# device-radiator-fan.net
KiCad netlist of a schematic drawn in Altium Designer
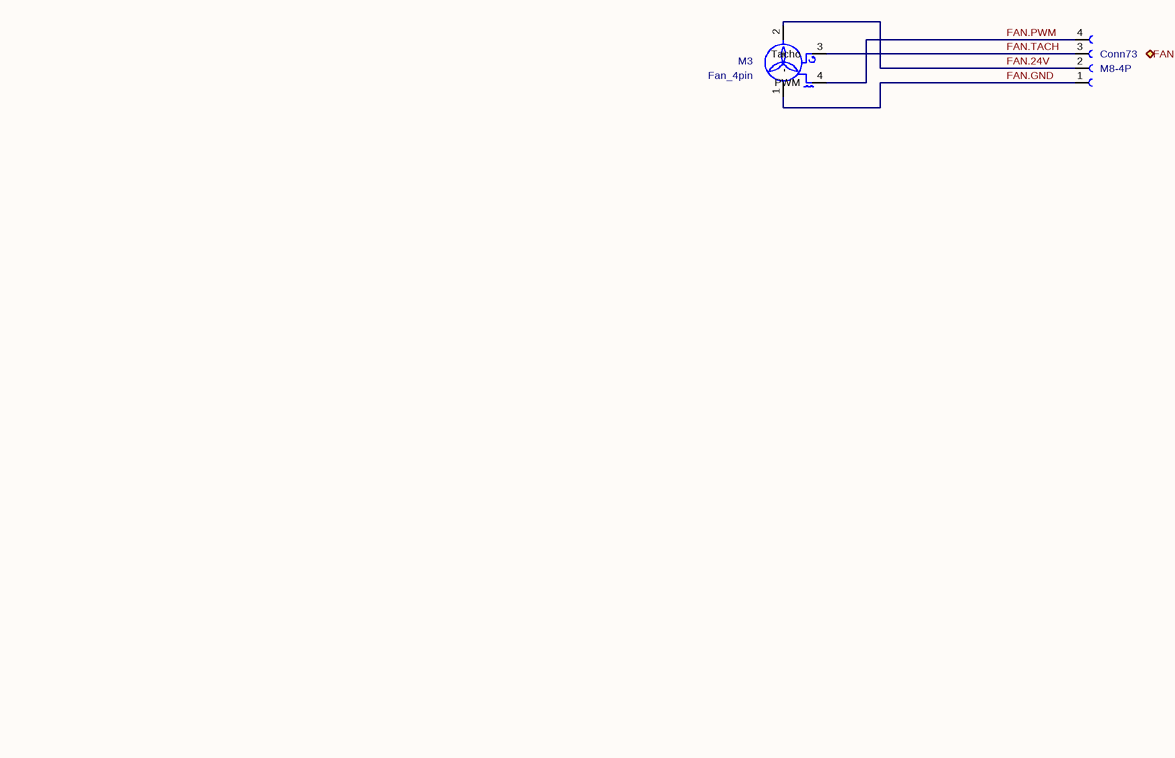
[diagram p0: device-radiator-fan.SchDoc]

(export (version "E")
  (design (tool "Eeschema 10.0.6"))
  (components
    (comp (ref "Conn73")
      (value "Deutsch_DTM_4S_Pin")
      (fields (field (name "P/N") "M8-4P"))
      (libsource (lib "Connectors_SUFST") (part "Deutsch_DTM_4S_Pin"))
    )
    (comp (ref "M3")
      (value "Fan_4pin")
      (footprint "FanPinHeader_1x04_P2.54mm_Vertical")
      (description "Fan, tacho output, PWM input, 4-pin connector")
      (libsource (lib "Motor") (part "Fan_4pin"))
    )
  )
  (nets
    (net (code "2") (name "/FAN.24V") (class "Default")
      (node (ref "Conn73") (pin "2") (pinfunction "2_2") (pintype "passive"))
      (node (ref "M3") (pin "2") (pinfunction "+_2") (pintype "passive"))
    )
    (net (code "3") (name "/FAN.GND") (class "Default")
      (node (ref "Conn73") (pin "1") (pinfunction "1_1") (pintype "passive"))
      (node (ref "M3") (pin "1") (pinfunction "-_1") (pintype "passive"))
    )
    (net (code "4") (name "/FAN.PWM") (class "Default")
      (node (ref "Conn73") (pin "4") (pinfunction "4_4") (pintype "passive"))
      (node (ref "M3") (pin "4") (pinfunction "PWM_4") (pintype "passive"))
    )
    (net (code "5") (name "/FAN.TACH") (class "Default")
      (node (ref "Conn73") (pin "3") (pinfunction "3_3") (pintype "passive"))
      (node (ref "M3") (pin "3") (pinfunction "Tacho_3") (pintype "passive"))
    )
  )
)
